# Encoder_Interface.net
KiCad netlist of a schematic drawn in Altium Designer
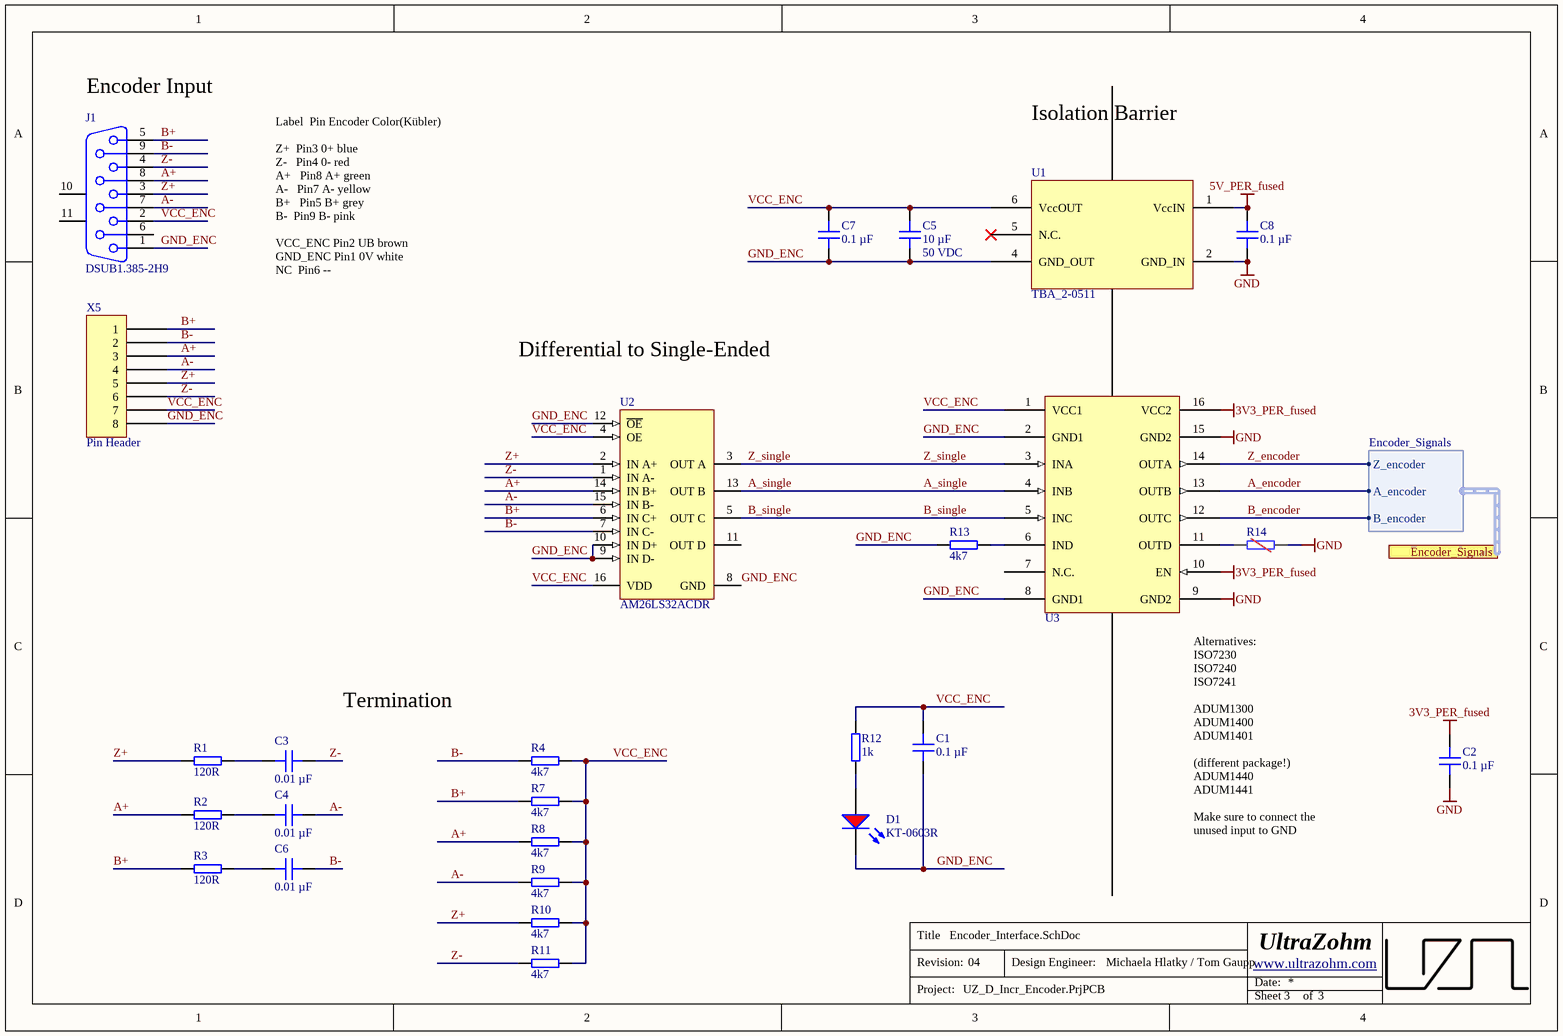
[diagram p0: Encoder_Interface.SchDoc]

(export (version "E")
  (design (tool "Eeschema 10.0.6"))
  (components
    (comp (ref "C1")
      (value "0.1 µF")
      (footprint "C_0805")
      (description "Capacitor 0805, 50 VDC, 0.1 µF, X7R")
      (fields
        (field (name "MANUFACTURER PART NUMBER") "C0805C104J5RECTU")
        (field (name "MANUFACTURER") "KEMET")
        (field (name "CREATED FROM") "MGremer")
      )
      (libsource (lib "user") (part "Capacitor"))
    )
    (comp (ref "C2")
      (value "0.1 µF")
      (footprint "C_0805")
      (description "Capacitor 0805, 50 VDC, 0.1 µF, X7R")
      (fields
        (field (name "MANUFACTURER PART NUMBER") "C0805C104J5RECTU")
        (field (name "MANUFACTURER") "KEMET")
        (field (name "CREATED FROM") "MGremer")
      )
      (libsource (lib "user") (part "Capacitor"))
    )
    (comp (ref "C3")
      (value "0.01 µF")
      (footprint "C_0805")
      (description "Capacitor 0805, 50 VDC, 0.01 µF, X7R")
      (fields
        (field (name "MANUFACTURER PART NUMBER") "C0805X103K5RAC3316")
        (field (name "MANUFACTURER") "KEMET")
        (field (name "CREATED FROM") "MGremer")
      )
      (libsource (lib "user") (part "Capacitor"))
    )
    (comp (ref "C4")
      (value "0.01 µF")
      (footprint "C_0805")
      (description "Capacitor 0805, 50 VDC, 0.01 µF, X7R")
      (fields
        (field (name "MANUFACTURER PART NUMBER") "C0805X103K5RAC3316")
        (field (name "MANUFACTURER") "KEMET")
        (field (name "CREATED FROM") "MGremer")
      )
      (libsource (lib "user") (part "Capacitor"))
    )
    (comp (ref "C5")
      (value "10 µF")
      (footprint "C_1206")
      (description "Capacitor 1206, 50 VDC, 10 µF, X7R")
      (fields
        (field (name "MANUFACTURER PART NUMBER") "CGA5L1X7R1H106K160AC")
        (field (name "MANUFACTURER") "TDK")
        (field (name "VOLTAGE RATING") "50 VDC")
        (field (name "CREATED FROM") "MGremer")
      )
      (libsource (lib "user") (part "Capacitor"))
    )
    (comp (ref "C6")
      (value "0.01 µF")
      (footprint "C_0805")
      (description "Capacitor 0805, 50 VDC, 0.01 µF, X7R")
      (fields
        (field (name "MANUFACTURER PART NUMBER") "C0805X103K5RAC3316")
        (field (name "MANUFACTURER") "KEMET")
        (field (name "CREATED FROM") "MGremer")
      )
      (libsource (lib "user") (part "Capacitor"))
    )
    (comp (ref "C7")
      (value "0.1 µF")
      (footprint "C_0805")
      (description "Capacitor 0805, 50 VDC, 0.1 µF, X7R")
      (fields
        (field (name "MANUFACTURER PART NUMBER") "C0805C104J5RECTU")
        (field (name "MANUFACTURER") "KEMET")
        (field (name "CREATED FROM") "MGremer")
      )
      (libsource (lib "user") (part "Capacitor"))
    )
    (comp (ref "C8")
      (value "0.1 µF")
      (footprint "C_0805")
      (description "Capacitor 0805, 50 VDC, 0.1 µF, X7R")
      (fields
        (field (name "MANUFACTURER PART NUMBER") "C0805C104J5RECTU")
        (field (name "MANUFACTURER") "KEMET")
        (field (name "CREATED FROM") "MGremer")
      )
      (libsource (lib "user") (part "Capacitor"))
    )
    (comp (ref "D1")
      (value "KT-0603R")
      (footprint "WL-SMCW_0603")
      (description "LED RED 520~625NM 90~100MCD@20MA TOP VIEW 0603 ROHS")
      (fields
        (field (name "MANUFACTURER") "Hubei KENTO Elec")
        (field (name "LCSC PART NUMBER") "C2286")
        (field (name "CREATED FROM") "T. Wendt")
      )
      (libsource (lib "user") (part "LED_Red"))
    )
    (comp (ref "J1")
      (value "DSUB1.385-2H9")
      (footprint "DSUB1.385-2H9")
      (description "Connector; D Subminiature; 9 Position; Right Angle; Pitch 1.385 mm")
      (fields
        (field (name "MANUFACTURER") "TE Connectivity")
        (field (name "LCSC PART NUMBER") "C141882")
        (field (name "PUBLISHER") "Altium Limited")
        (field (name "CREATED FROM") "MHlatky")
      )
      (libsource (lib "user") (part "D Connector 9"))
    )
    (comp (ref "R1")
      (value "120R")
      (footprint "RES 0603_1608")
      (description "SMD resistor E24 series")
      (fields
        (field (name "MANUFACTURER PART NUMBER") "RK73B1JTTD121J")
        (field (name "MANUFACTURER") "KOA Speer")
        (field (name "CREATED FROM") "MGremer")
      )
      (libsource (lib "user") (part "Resistor"))
    )
    (comp (ref "R2")
      (value "120R")
      (footprint "RES 0603_1608")
      (description "SMD resistor E24 series")
      (fields
        (field (name "MANUFACTURER PART NUMBER") "RK73B1JTTD121J")
        (field (name "MANUFACTURER") "KOA Speer")
        (field (name "CREATED FROM") "MGremer")
      )
      (libsource (lib "user") (part "Resistor"))
    )
    (comp (ref "R3")
      (value "120R")
      (footprint "RES 0603_1608")
      (description "SMD resistor E24 series")
      (fields
        (field (name "MANUFACTURER PART NUMBER") "RK73B1JTTD121J")
        (field (name "MANUFACTURER") "KOA Speer")
        (field (name "CREATED FROM") "MGremer")
      )
      (libsource (lib "user") (part "Resistor"))
    )
    (comp (ref "R4")
      (value "4k7")
      (footprint "RES 0603_1608")
      (description "SMD resistor E24 series")
      (fields
        (field (name "MANUFACTURER PART NUMBER") "RK73B1JTTD472J")
        (field (name "MANUFACTURER") "KOA Speer")
        (field (name "CREATED FROM") "MGremer")
      )
      (libsource (lib "user") (part "Resistor"))
    )
    (comp (ref "R7")
      (value "4k7")
      (footprint "RES 0603_1608")
      (description "SMD resistor E24 series")
      (fields
        (field (name "MANUFACTURER PART NUMBER") "RK73B1JTTD472J")
        (field (name "MANUFACTURER") "KOA Speer")
        (field (name "CREATED FROM") "MGremer")
      )
      (libsource (lib "user") (part "Resistor"))
    )
    (comp (ref "R8")
      (value "4k7")
      (footprint "RES 0603_1608")
      (description "SMD resistor E24 series")
      (fields
        (field (name "MANUFACTURER PART NUMBER") "RK73B1JTTD472J")
        (field (name "MANUFACTURER") "KOA Speer")
        (field (name "CREATED FROM") "MGremer")
      )
      (libsource (lib "user") (part "Resistor"))
    )
    (comp (ref "R9")
      (value "4k7")
      (footprint "RES 0603_1608")
      (description "SMD resistor E24 series")
      (fields
        (field (name "MANUFACTURER PART NUMBER") "RK73B1JTTD472J")
        (field (name "MANUFACTURER") "KOA Speer")
        (field (name "CREATED FROM") "MGremer")
      )
      (libsource (lib "user") (part "Resistor"))
    )
    (comp (ref "R10")
      (value "4k7")
      (footprint "RES 0603_1608")
      (description "SMD resistor E24 series")
      (fields
        (field (name "MANUFACTURER PART NUMBER") "RK73B1JTTD472J")
        (field (name "MANUFACTURER") "KOA Speer")
        (field (name "CREATED FROM") "MGremer")
      )
      (libsource (lib "user") (part "Resistor"))
    )
    (comp (ref "R11")
      (value "4k7")
      (footprint "RES 0603_1608")
      (description "SMD resistor E24 series")
      (fields
        (field (name "MANUFACTURER PART NUMBER") "RK73B1JTTD472J")
        (field (name "MANUFACTURER") "KOA Speer")
        (field (name "CREATED FROM") "MGremer")
      )
      (libsource (lib "user") (part "Resistor"))
    )
    (comp (ref "R12")
      (value "1k")
      (footprint "RES 0603_1608")
      (description "SMD resistor E24 series")
      (fields
        (field (name "MANUFACTURER PART NUMBER") "RK73B1JTTDD102J")
        (field (name "MANUFACTURER") "KOA Speer")
        (field (name "CREATED FROM") "MGremer")
      )
      (libsource (lib "user") (part "Resistor"))
    )
    (comp (ref "R13")
      (value "4k7")
      (footprint "RES 0603_1608")
      (description "SMD resistor E24 series")
      (fields
        (field (name "MANUFACTURER PART NUMBER") "RK73B1JTTD472J")
        (field (name "MANUFACTURER") "KOA Speer")
        (field (name "CREATED FROM") "MGremer")
      )
      (libsource (lib "user") (part "Resistor"))
    )
    (comp (ref "R14")
      (value "DNP")
      (footprint "R_0603_TE-DNP")
      (description "Generic resistor (DNP)")
      (fields
        (field (name "MANUFACTURER PART NUMBER") "UZgen_R_0603_DNP")
        (field (name "MANUFACTURER") "UZgen")
        (field (name "CREATED FROM") "UZgenTool")
      )
      (libsource (lib "user") (part "RES-DNP"))
    )
    (comp (ref "U1")
      (value "TBA_2-0511")
      (footprint "SIP7")
      (description "4.5-5.5 V Input, 5 V @ 400 mA Output, 2 W, isolated DC/DC-converter")
      (fields
        (field (name "MANUFACTURER") "TRACO Power")
        (field (name "LCSC PART NUMBER") "C6329167")
        (field (name "CREATED FROM") "TGaupp")
      )
      (libsource (lib "user") (part "TBA_2-0511"))
    )
    (comp (ref "U2")
      (value "AM26LS32ACDR")
      (footprint "D0016A_M")
      (description "AM26LS32Ax, AM26LS33Ax Quadruple Differential Line Receivers")
      (fields
        (field (name "PARTNUMBER") "DS26LS32ACM")
        (field (name "MANUFACTURER") "Texas Instruments")
        (field (name "PUBLISHER") "Altium Limited")
        (field (name "CREATED FROM") "MHlatky")
      )
      (libsource (lib "user") (part "AM26LS32ACDR"))
    )
    (comp (ref "U3")
      (value "ISO7240MDWR")
      (footprint "SOIC-16")
      (description "ISO7240x Quad Ch 4  150Mbps Digital Isolator")
      (fields
        (field (name "MANUFACTURER") "Texas Instruments")
        (field (name "LCSC PART NUMBER") "C37709")
        (field (name "CREATED FROM") "TGaupp")
      )
      (libsource (lib "user") (part "ISO7240"))
    )
    (comp (ref "X5")
      (value "Pin Header")
      (footprint "HDR1X8")
      (description "8 Pin")
      (fields
        (field (name "MANUFACTURER PART NUMBER") "103741-8")
        (field (name "MANUFACTURER") "TE Connectivity")
        (field (name "CREATED FROM") "MHlatky")
      )
      (libsource (lib "user") (part "8 Pin"))
    )
  )
  (nets
    (net (code "2") (name "/A+") (class "Default")
      (node (ref "J1") (pin "8") (pinfunction "8_8") (pintype "passive"))
      (node (ref "R2") (pin "1") (pinfunction "1_1") (pintype "passive"))
      (node (ref "R8") (pin "1") (pinfunction "1_1") (pintype "passive"))
      (node (ref "U2") (pin "14") (pinfunction "IN_B+_14") (pintype "input"))
      (node (ref "X5") (pin "3") (pinfunction "3_3") (pintype "passive"))
    )
    (net (code "3") (name "/A-") (class "Default")
      (node (ref "C4") (pin "2") (pinfunction "2_2") (pintype "passive"))
      (node (ref "J1") (pin "7") (pinfunction "7_7") (pintype "passive"))
      (node (ref "R9") (pin "1") (pinfunction "1_1") (pintype "passive"))
      (node (ref "U2") (pin "15") (pinfunction "IN_B-_15") (pintype "input"))
      (node (ref "X5") (pin "4") (pinfunction "4_4") (pintype "passive"))
    )
    (net (code "4") (name "/A_encoder") (class "Default")
      (node (ref "U3") (pin "13") (pinfunction "OUTB_13") (pintype "output"))
    )
    (net (code "5") (name "/A_single") (class "Default")
      (node (ref "U2") (pin "13") (pinfunction "OUT_B_13") (pintype "tri_state"))
      (node (ref "U3") (pin "4") (pinfunction "INB_4") (pintype "input"))
    )
    (net (code "6") (name "/B+") (class "Default")
      (node (ref "J1") (pin "5") (pinfunction "5_5") (pintype "passive"))
      (node (ref "R3") (pin "1") (pinfunction "1_1") (pintype "passive"))
      (node (ref "R7") (pin "1") (pinfunction "1_1") (pintype "passive"))
      (node (ref "U2") (pin "6") (pinfunction "IN_C+_6") (pintype "input"))
      (node (ref "X5") (pin "1") (pinfunction "1_1") (pintype "passive"))
    )
    (net (code "7") (name "/B-") (class "Default")
      (node (ref "C6") (pin "2") (pinfunction "2_2") (pintype "passive"))
      (node (ref "J1") (pin "9") (pinfunction "9_9") (pintype "passive"))
      (node (ref "R4") (pin "1") (pinfunction "1_1") (pintype "passive"))
      (node (ref "U2") (pin "7") (pinfunction "IN_C-_7") (pintype "input"))
      (node (ref "X5") (pin "2") (pinfunction "2_2") (pintype "passive"))
    )
    (net (code "8") (name "/B_encoder") (class "Default")
      (node (ref "U3") (pin "12") (pinfunction "OUTC_12") (pintype "output"))
    )
    (net (code "9") (name "/B_single") (class "Default")
      (node (ref "U2") (pin "5") (pinfunction "OUT_C_5") (pintype "tri_state"))
      (node (ref "U3") (pin "5") (pinfunction "INC_5") (pintype "input"))
    )
    (net (code "10") (name "/GND_ENC") (class "Default")
      (node (ref "C1") (pin "1") (pinfunction "1_1") (pintype "passive"))
      (node (ref "C5") (pin "1") (pinfunction "1_1") (pintype "passive"))
      (node (ref "C7") (pin "1") (pinfunction "1_1") (pintype "passive"))
      (node (ref "D1") (pin "1") (pinfunction "K_1") (pintype "passive"))
      (node (ref "J1") (pin "1") (pinfunction "1_1") (pintype "passive"))
      (node (ref "R13") (pin "1") (pinfunction "1_1") (pintype "passive"))
      (node (ref "U1") (pin "4") (pinfunction "GND_OUT_4") (pintype "power_in"))
      (node (ref "U2") (pin "10") (pinfunction "IN_D+_10") (pintype "input"))
      (node (ref "U2") (pin "12") (pinfunction "~{OE}_12") (pintype "input"))
      (node (ref "U2") (pin "8") (pinfunction "GND_8") (pintype "power_in"))
      (node (ref "U2") (pin "9") (pinfunction "IN_D-_9") (pintype "input"))
      (node (ref "U3") (pin "2") (pinfunction "GND1_2") (pintype "passive"))
      (node (ref "U3") (pin "8") (pinfunction "GND1_8") (pintype "power_in"))
      (node (ref "X5") (pin "8") (pinfunction "8_8") (pintype "passive"))
    )
    (net (code "11") (name "/VCC_ENC") (class "Default")
      (node (ref "C1") (pin "2") (pinfunction "2_2") (pintype "passive"))
      (node (ref "C5") (pin "2") (pinfunction "2_2") (pintype "passive"))
      (node (ref "C7") (pin "2") (pinfunction "2_2") (pintype "passive"))
      (node (ref "J1") (pin "2") (pinfunction "2_2") (pintype "passive"))
      (node (ref "R10") (pin "2") (pinfunction "2_2") (pintype "passive"))
      (node (ref "R11") (pin "2") (pinfunction "2_2") (pintype "passive"))
      (node (ref "R12") (pin "2") (pinfunction "2_2") (pintype "passive"))
      (node (ref "R4") (pin "2") (pinfunction "2_2") (pintype "passive"))
      (node (ref "R7") (pin "2") (pinfunction "2_2") (pintype "passive"))
      (node (ref "R8") (pin "2") (pinfunction "2_2") (pintype "passive"))
      (node (ref "R9") (pin "2") (pinfunction "2_2") (pintype "passive"))
      (node (ref "U1") (pin "6") (pinfunction "VccOUT_6") (pintype "power_in"))
      (node (ref "U2") (pin "16") (pinfunction "VDD_16") (pintype "power_in"))
      (node (ref "U2") (pin "4") (pinfunction "OE_4") (pintype "input"))
      (node (ref "U3") (pin "1") (pinfunction "VCC1_1") (pintype "power_in"))
      (node (ref "X5") (pin "7") (pinfunction "7_7") (pintype "passive"))
    )
    (net (code "12") (name "/Z+") (class "Default")
      (node (ref "J1") (pin "3") (pinfunction "3_3") (pintype "passive"))
      (node (ref "R1") (pin "1") (pinfunction "1_1") (pintype "passive"))
      (node (ref "R10") (pin "1") (pinfunction "1_1") (pintype "passive"))
      (node (ref "U2") (pin "2") (pinfunction "IN_A+_2") (pintype "input"))
      (node (ref "X5") (pin "5") (pinfunction "5_5") (pintype "passive"))
    )
    (net (code "13") (name "/Z-") (class "Default")
      (node (ref "C3") (pin "2") (pinfunction "2_2") (pintype "passive"))
      (node (ref "J1") (pin "4") (pinfunction "4_4") (pintype "passive"))
      (node (ref "R11") (pin "1") (pinfunction "1_1") (pintype "passive"))
      (node (ref "U2") (pin "1") (pinfunction "IN_A-_1") (pintype "input"))
      (node (ref "X5") (pin "6") (pinfunction "6_6") (pintype "passive"))
    )
    (net (code "14") (name "/Z_encoder") (class "Default")
      (node (ref "U3") (pin "14") (pinfunction "OUTA_14") (pintype "output"))
    )
    (net (code "15") (name "/Z_single") (class "Default")
      (node (ref "U2") (pin "3") (pinfunction "OUT_A_3") (pintype "tri_state"))
      (node (ref "U3") (pin "3") (pinfunction "INA_3") (pintype "input"))
    )
    (net (code "17") (name "3V3_PER_fused") (class "Default")
      (node (ref "C2") (pin "2") (pinfunction "2_2") (pintype "passive"))
      (node (ref "U3") (pin "10") (pinfunction "EN_10") (pintype "input"))
      (node (ref "U3") (pin "16") (pinfunction "VCC2_16") (pintype "power_in"))
    )
    (net (code "18") (name "5V_PER_fused") (class "Default")
      (node (ref "C8") (pin "2") (pinfunction "2_2") (pintype "passive"))
      (node (ref "U1") (pin "1") (pinfunction "VccIN_1") (pintype "power_in"))
    )
    (net (code "19") (name "GND") (class "Default")
      (node (ref "C2") (pin "1") (pinfunction "1_1") (pintype "passive"))
      (node (ref "C8") (pin "1") (pinfunction "1_1") (pintype "passive"))
      (node (ref "R14") (pin "2") (pinfunction "2_2") (pintype "passive"))
      (node (ref "U1") (pin "2") (pinfunction "GND_IN_2") (pintype "power_in"))
      (node (ref "U3") (pin "15") (pinfunction "GND2_15") (pintype "passive"))
      (node (ref "U3") (pin "9") (pinfunction "GND2_9") (pintype "power_in"))
    )
    (net (code "20") (name "Net-(C3-Pad1)") (class "Default")
      (node (ref "C3") (pin "1") (pinfunction "1_1") (pintype "passive"))
      (node (ref "R1") (pin "2") (pinfunction "2_2") (pintype "passive"))
    )
    (net (code "21") (name "Net-(C4-Pad1)") (class "Default")
      (node (ref "C4") (pin "1") (pinfunction "1_1") (pintype "passive"))
      (node (ref "R2") (pin "2") (pinfunction "2_2") (pintype "passive"))
    )
    (net (code "22") (name "Net-(C6-Pad1)") (class "Default")
      (node (ref "C6") (pin "1") (pinfunction "1_1") (pintype "passive"))
      (node (ref "R3") (pin "2") (pinfunction "2_2") (pintype "passive"))
    )
    (net (code "23") (name "Net-(D1-A)") (class "Default")
      (node (ref "D1") (pin "2") (pinfunction "A_2") (pintype "passive"))
      (node (ref "R12") (pin "1") (pinfunction "1_1") (pintype "passive"))
    )
    (net (code "24") (name "Net-(U3-IND)") (class "Default")
      (node (ref "R13") (pin "2") (pinfunction "2_2") (pintype "passive"))
      (node (ref "U3") (pin "6") (pinfunction "IND_6") (pintype "passive"))
    )
    (net (code "25") (name "Net-(U3-OUTD)") (class "Default")
      (node (ref "R14") (pin "1") (pinfunction "1_1") (pintype "passive"))
      (node (ref "U3") (pin "11") (pinfunction "OUTD_11") (pintype "passive"))
    )
    (net (code "26") (name "unconnected-(J1-MH1-Pad10)") (class "Default")
      (node (ref "J1") (pin "10") (pinfunction "MH1_10") (pintype "passive"))
    )
    (net (code "27") (name "unconnected-(J1-MH2-Pad11)") (class "Default")
      (node (ref "J1") (pin "11") (pinfunction "MH2_11") (pintype "passive"))
    )
    (net (code "28") (name "unconnected-(J1-Pad6)") (class "Default")
      (node (ref "J1") (pin "6") (pinfunction "6_6") (pintype "passive"))
    )
    (net (code "29") (name "unconnected-(U1-N.C.-Pad5)") (class "Default")
      (node (ref "U1") (pin "5") (pinfunction "N.C._5") (pintype "passive+no_connect"))
    )
    (net (code "30") (name "unconnected-(U2-OUT_D-Pad11)") (class "Default")
      (node (ref "U2") (pin "11") (pinfunction "OUT_D_11") (pintype "tri_state"))
    )
    (net (code "31") (name "unconnected-(U3-N.C.-Pad7)") (class "Default")
      (node (ref "U3") (pin "7") (pinfunction "N.C._7") (pintype "passive"))
    )
  )
)
